# ws2811-Breakout.net
KiCad netlist of a schematic drawn in EAGLE
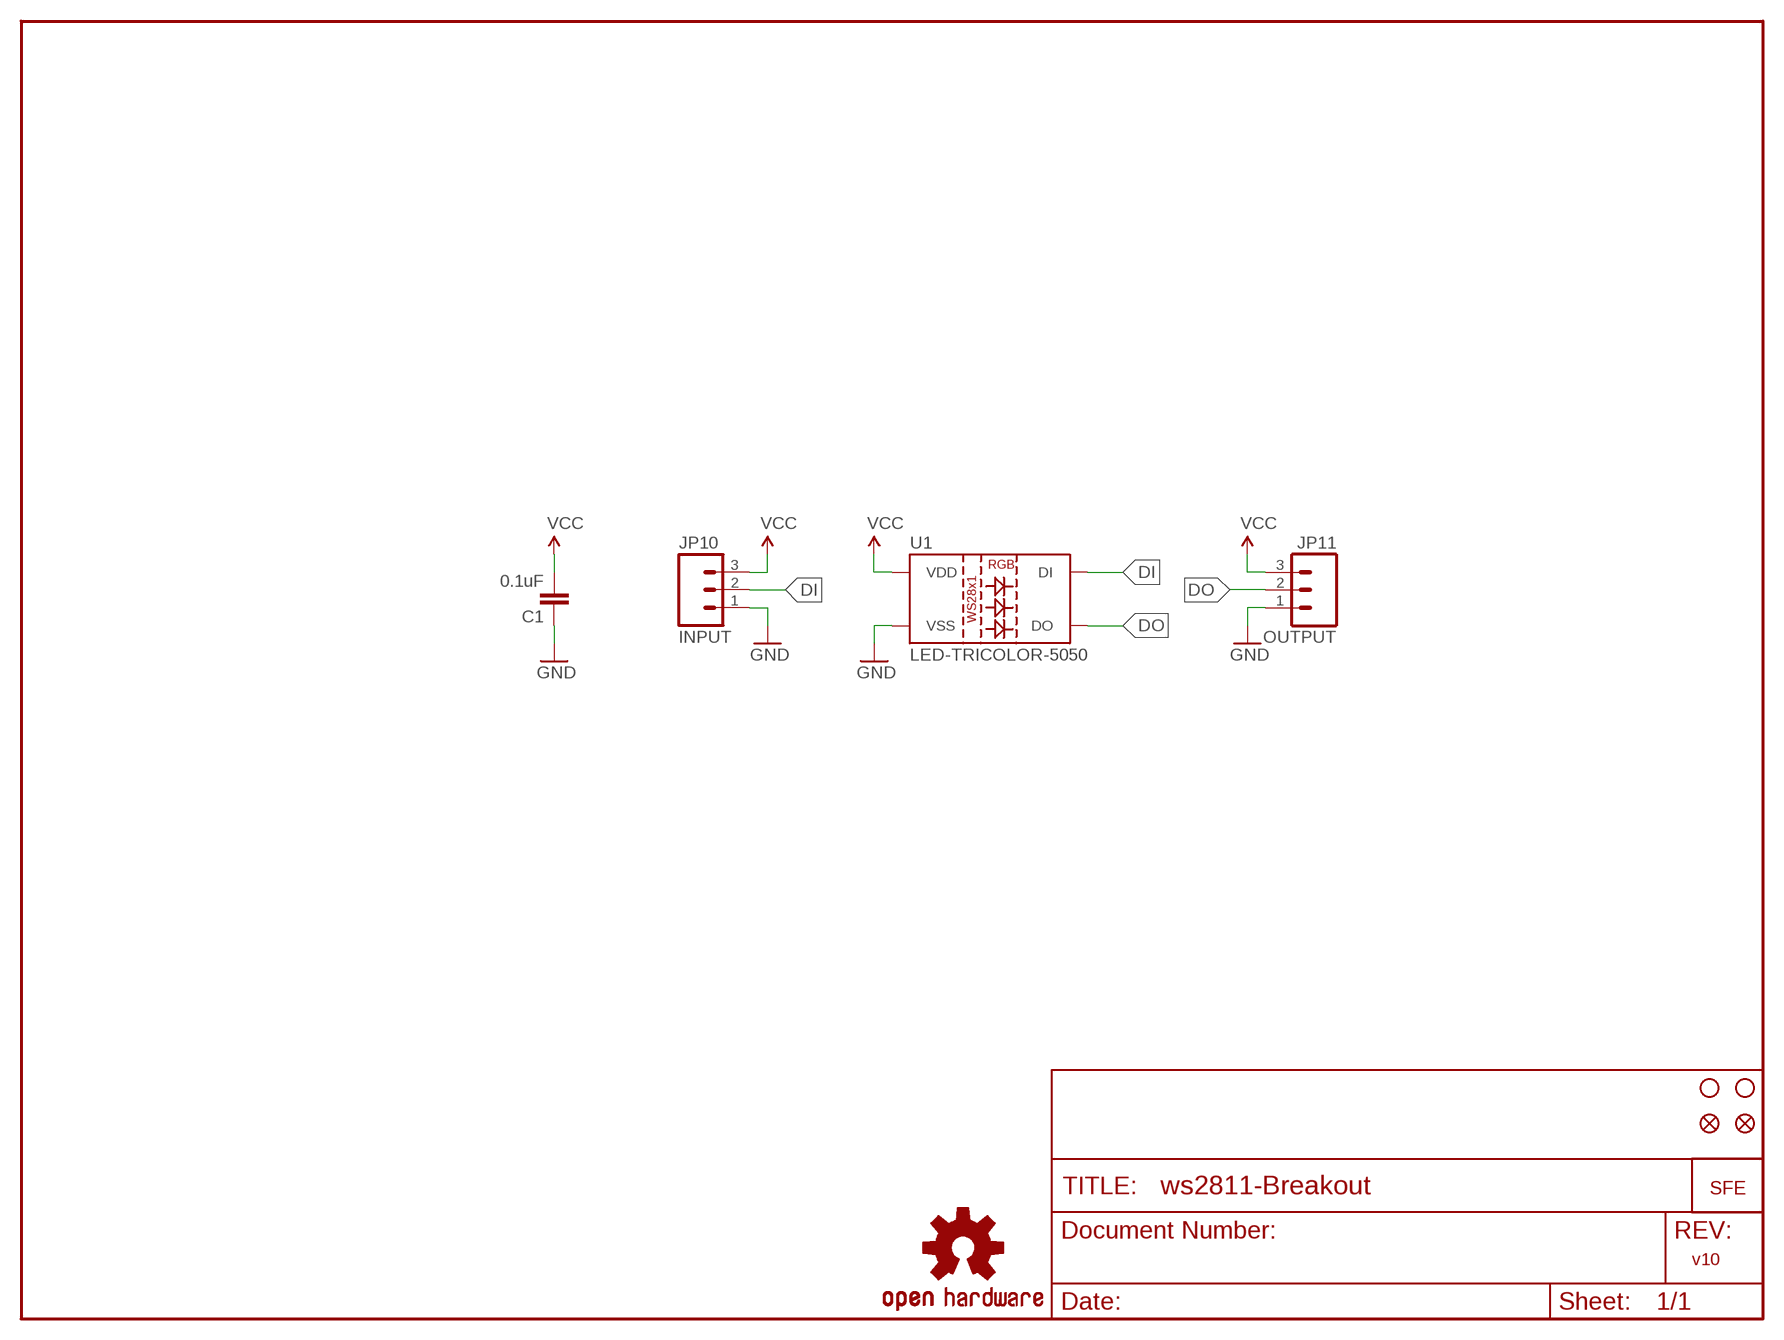
[diagram p0: schematic, sheet 1]

(export (version "E")
  (design (tool "Eeschema 10.0.6"))
  (components
    (comp (ref "C1")
      (value "0.1uF")
      (footprint "eagle-import:0603-CAP")
      (libsource (lib "eagle-import") (part "CAP0603-CAP"))
    )
    (comp (ref "FID1")
      (value "FIDUCIALUFIDUCIAL")
      (footprint "eagle-import:MICRO-FIDUCIAL")
      (libsource (lib "eagle-import") (part "FIDUCIALUFIDUCIAL"))
    )
    (comp (ref "FID2")
      (value "FIDUCIALUFIDUCIAL")
      (footprint "eagle-import:MICRO-FIDUCIAL")
      (libsource (lib "eagle-import") (part "FIDUCIALUFIDUCIAL"))
    )
    (comp (ref "JP1")
      (value "STAND-OFF")
      (footprint "eagle-import:STAND-OFF")
      (libsource (lib "eagle-import") (part "STAND-OFF"))
    )
    (comp (ref "JP3")
      (value "LOGO-SFESK")
      (footprint "eagle-import:SFE-LOGO-FLAME")
      (libsource (lib "eagle-import") (part "LOGO-SFESK"))
    )
    (comp (ref "JP4")
      (value "STAND-OFF")
      (footprint "eagle-import:STAND-OFF")
      (libsource (lib "eagle-import") (part "STAND-OFF"))
    )
    (comp (ref "JP10")
      (value "INPUT")
      (footprint "eagle-import:1X03")
      (libsource (lib "eagle-import") (part "M03PTH"))
    )
    (comp (ref "JP11")
      (value "OUTPUT")
      (footprint "eagle-import:1X03")
      (libsource (lib "eagle-import") (part "M03PTH"))
    )
    (comp (ref "LOGO1")
      (value "OSHW-LOGOS")
      (footprint "eagle-import:OSHW-LOGO-S")
      (libsource (lib "eagle-import") (part "OSHW-LOGOS"))
    )
    (comp (ref "U1")
      (value "LED-TRICOLOR-5050")
      (footprint "eagle-import:LED-TRICOLOR-5050-IC")
      (libsource (lib "eagle-import") (part "LED-TRICOLOR-5050-ICWS2811"))
    )
  )
  (nets
    (net (code "1") (name "DI") (class "Default")
      (node (ref "JP10") (pin "2") (pinfunction "2_2") (pintype "passive"))
      (node (ref "U1") (pin "2") (pinfunction "DI_2") (pintype "bidirectional"))
    )
    (net (code "2") (name "DO") (class "Default")
      (node (ref "JP11") (pin "2") (pinfunction "2_2") (pintype "passive"))
      (node (ref "U1") (pin "1") (pinfunction "DO_1") (pintype "bidirectional"))
    )
    (net (code "3") (name "GND") (class "Default")
      (node (ref "C1") (pin "1") (pinfunction "1_1") (pintype "passive"))
      (node (ref "JP10") (pin "1") (pinfunction "1_1") (pintype "passive"))
      (node (ref "JP11") (pin "1") (pinfunction "1_1") (pintype "passive"))
      (node (ref "U1") (pin "6") (pinfunction "VSS_6") (pintype "bidirectional"))
    )
    (net (code "4") (name "VCC") (class "Default")
      (node (ref "C1") (pin "2") (pinfunction "2_2") (pintype "passive"))
      (node (ref "JP10") (pin "3") (pinfunction "3_3") (pintype "passive"))
      (node (ref "JP11") (pin "3") (pinfunction "3_3") (pintype "passive"))
      (node (ref "U1") (pin "3") (pinfunction "VDD_3") (pintype "bidirectional"))
      (node (ref "U1") (pin "5") (pinfunction "VDD_5") (pintype "bidirectional"))
    )
  )
)
